# Power.net
KiCad netlist of a schematic drawn in Altium Designer
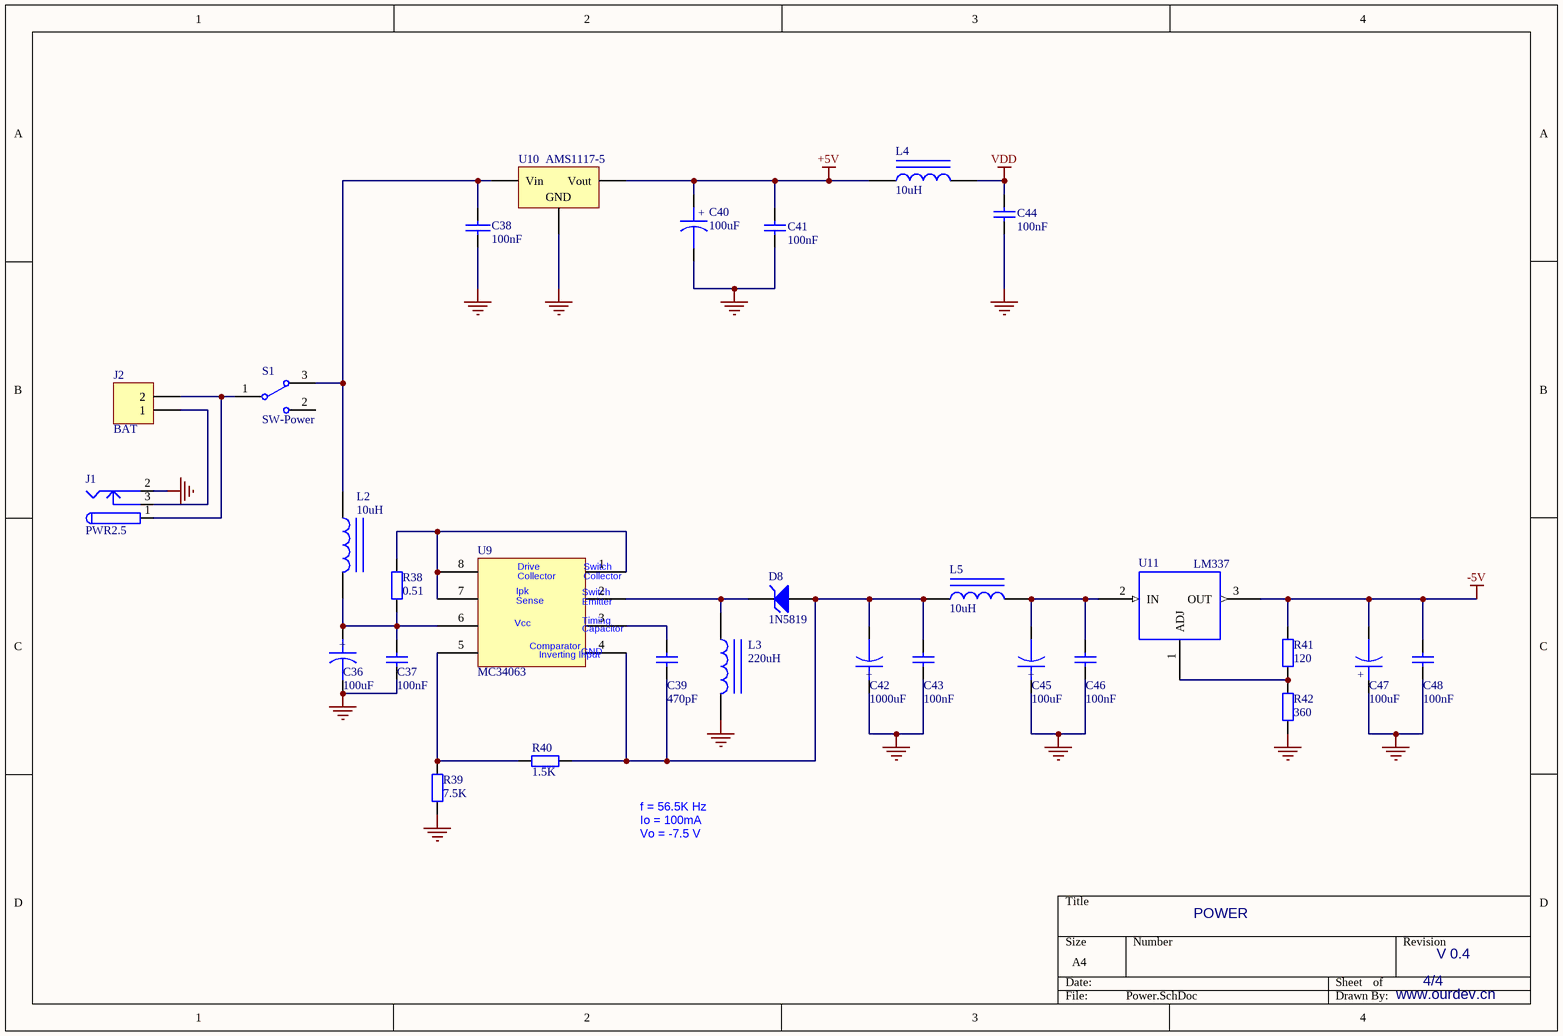
[diagram p0: Power.SchDoc]

(export (version "E")
  (design (tool "Eeschema 10.0.6"))
  (components
    (comp (ref "C36")
      (value "100uF")
      (footprint "Cap 3X6")
      (description "Capacitor")
      (libsource (lib "*") (part "CAPACITOR POL"))
    )
    (comp (ref "C37")
      (value "100nF")
      (footprint "CC2012-0805")
      (description "Capacitor")
      (fields (field (name "PUBLISHER") "Altium Limited"))
      (libsource (lib "*") (part "Cap"))
    )
    (comp (ref "C38")
      (value "100nF")
      (footprint "CC2012-0805")
      (description "Capacitor")
      (libsource (lib "*") (part "CAP"))
    )
    (comp (ref "C39")
      (value "470pF")
      (footprint "CC2012-0805")
      (description "Capacitor")
      (fields (field (name "PUBLISHER") "Altium Limited"))
      (libsource (lib "*") (part "Cap"))
    )
    (comp (ref "C40")
      (value "100uF")
      (footprint "Cap 3X6")
      (description "Capacitor")
      (libsource (lib "") (part "CAPACITOR POL_1"))
    )
    (comp (ref "C41")
      (value "100nF")
      (footprint "CC2012-0805")
      (description "Capacitor")
      (fields (field (name "PUBLISHER") "Altium Limited"))
      (libsource (lib "*") (part "Cap"))
    )
    (comp (ref "C42")
      (value "1000uF")
      (footprint "Cap 3X6")
      (description "Capacitor")
      (libsource (lib "*") (part "CAPACITOR POL"))
    )
    (comp (ref "C43")
      (value "100nF")
      (footprint "CC2012-0805")
      (description "Capacitor")
      (fields (field (name "PUBLISHER") "Altium Limited"))
      (libsource (lib "*") (part "Cap"))
    )
    (comp (ref "C44")
      (value "100nF")
      (footprint "CC2012-0805")
      (description "Capacitor")
      (fields (field (name "PUBLISHER") "Altium Limited"))
      (libsource (lib "*") (part "Cap"))
    )
    (comp (ref "C45")
      (value "100uF")
      (footprint "Cap 3X6")
      (description "Capacitor")
      (libsource (lib "*") (part "CAPACITOR POL"))
    )
    (comp (ref "C46")
      (value "100nF")
      (footprint "CC2012-0805")
      (description "Capacitor")
      (fields (field (name "PUBLISHER") "Altium Limited"))
      (libsource (lib "*") (part "Cap"))
    )
    (comp (ref "C47")
      (value "100uF")
      (footprint "Cap 3X6")
      (description "Capacitor")
      (libsource (lib "") (part "CAPACITOR POL_1"))
    )
    (comp (ref "C48")
      (value "100nF")
      (footprint "CC2012-0805")
      (description "Capacitor")
      (fields (field (name "PUBLISHER") "Altium Limited"))
      (libsource (lib "*") (part "Cap"))
    )
    (comp (ref "D8")
      (value "1N5819")
      (footprint "SMC")
      (description "Zener Diode")
      (fields (field (name "PUBLISHER") "Altium Limited"))
      (libsource (lib "Miscellaneous Devices") (part "D Zener"))
    )
    (comp (ref "J1")
      (value "PWR2.5")
      (footprint "DC JACK")
      (description "Low Voltage Power Supply Connector")
      (fields (field (name "PUBLISHER") "Altium Limited"))
      (libsource (lib "Miscellaneous Connectors") (part "PWR2.5"))
    )
    (comp (ref "J2")
      (value "BAT")
      (footprint "HDR1X2")
      (description "Header, 2-Pin")
      (fields (field (name "PUBLISHER") "Altium Limited"))
      (libsource (lib "Miscellaneous Connectors") (part "Header 2"))
    )
    (comp (ref "L2")
      (value "10uH")
      (footprint "L1.4/3")
      (description "Magnetic-Core Inductor")
      (fields (field (name "PUBLISHER") "Altium Limited"))
      (libsource (lib "Miscellaneous Devices") (part "Inductor Iron"))
    )
    (comp (ref "L3")
      (value "220uH")
      (footprint "L1.4/3")
      (description "Magnetic-Core Inductor")
      (fields (field (name "PUBLISHER") "Altium Limited"))
      (libsource (lib "Miscellaneous Devices") (part "Inductor Iron"))
    )
    (comp (ref "L4")
      (value "10uH")
      (footprint "L1.4/3")
      (description "Magnetic-Core Inductor")
      (fields (field (name "PUBLISHER") "Altium Limited"))
      (libsource (lib "Miscellaneous Devices") (part "Inductor Iron"))
    )
    (comp (ref "L5")
      (value "10uH")
      (footprint "L1.4/3")
      (description "Magnetic-Core Inductor")
      (fields (field (name "PUBLISHER") "Altium Limited"))
      (libsource (lib "Miscellaneous Devices") (part "Inductor Iron"))
    )
    (comp (ref "R38")
      (value "0.51")
      (footprint "R-1206")
      (description "Resistor")
      (fields (field (name "PUBLISHER") "Altium Limited"))
      (libsource (lib "Miscellaneous Devices") (part "Res2"))
    )
    (comp (ref "R39")
      (value "7.5K")
      (footprint "CR2012-0805")
      (description "Resistor")
      (fields (field (name "PUBLISHER") "Altium Limited"))
      (libsource (lib "Miscellaneous Devices") (part "Res2"))
    )
    (comp (ref "R40")
      (value "1.5K")
      (footprint "CR2012-0805")
      (description "Resistor")
      (fields (field (name "PUBLISHER") "Altium Limited"))
      (libsource (lib "") (part "Res2_1"))
    )
    (comp (ref "R41")
      (value "120")
      (footprint "CR2012-0805")
      (description "Resistor")
      (fields (field (name "PUBLISHER") "Altium Limited"))
      (libsource (lib "Miscellaneous Devices") (part "Res2"))
    )
    (comp (ref "R42")
      (value "360")
      (footprint "CR2012-0805")
      (description "Resistor")
      (fields (field (name "PUBLISHER") "Altium Limited"))
      (libsource (lib "Miscellaneous Devices") (part "Res2"))
    )
    (comp (ref "S1")
      (value "SW-Power")
      (footprint "SW-6B")
      (description "SPDT Subminiature Toggle Switch, Right Angle Mounting, Vertical Actuation")
      (fields (field (name "PUBLISHER") "Altium Limited"))
      (libsource (lib "Miscellaneous Devices") (part "SW-SPDT"))
    )
    (comp (ref "U9") (value "MC34063") (footprint "SO-8") (libsource (lib "MC34063") (part "MC34063")))
    (comp (ref "U10")
      (value "AMS1117-5")
      (footprint "SOT-223")
      (description "Voltage Regulator")
      (fields (field (name "PUBLISHER") "Altium Limited"))
      (libsource (lib "Miscellaneous Devices") (part "Volt Reg"))
    )
    (comp (ref "U11") (value "LM337") (footprint "D2PAK") (libsource (lib "LM337") (part "LM337")))
  )
  (nets
    (net (code "1") (name "+5V") (class "Default")
      (node (ref "C40") (pin "1") (pinfunction "1_1") (pintype "passive"))
      (node (ref "C41") (pin "1") (pinfunction "1_1") (pintype "passive"))
      (node (ref "L4") (pin "1") (pinfunction "1_1") (pintype "passive"))
      (node (ref "U10") (pin "2") (pinfunction "Vout_2") (pintype "passive"))
    )
    (net (code "2") (name "-5V") (class "Default")
      (node (ref "C47") (pin "2") (pinfunction "2_2") (pintype "passive"))
      (node (ref "C48") (pin "1") (pinfunction "1_1") (pintype "passive"))
      (node (ref "R41") (pin "2") (pinfunction "2_2") (pintype "passive"))
      (node (ref "U11") (pin "3") (pinfunction "OUT_3") (pintype "output"))
    )
    (net (code "3") (name "GND") (class "Default")
      (node (ref "C36") (pin "2") (pinfunction "2_2") (pintype "passive"))
      (node (ref "C37") (pin "2") (pinfunction "2_2") (pintype "passive"))
      (node (ref "C38") (pin "2") (pinfunction "2_2") (pintype "passive"))
      (node (ref "C40") (pin "2") (pinfunction "2_2") (pintype "passive"))
      (node (ref "C41") (pin "2") (pinfunction "2_2") (pintype "passive"))
      (node (ref "C42") (pin "1") (pinfunction "1_1") (pintype "passive"))
      (node (ref "C43") (pin "2") (pinfunction "2_2") (pintype "passive"))
      (node (ref "C44") (pin "2") (pinfunction "2_2") (pintype "passive"))
      (node (ref "C45") (pin "1") (pinfunction "1_1") (pintype "passive"))
      (node (ref "C46") (pin "2") (pinfunction "2_2") (pintype "passive"))
      (node (ref "C47") (pin "1") (pinfunction "1_1") (pintype "passive"))
      (node (ref "C48") (pin "2") (pinfunction "2_2") (pintype "passive"))
      (node (ref "J1") (pin "2") (pinfunction "2_2") (pintype "power_in"))
      (node (ref "L3") (pin "2") (pinfunction "2_2") (pintype "passive"))
      (node (ref "R39") (pin "1") (pinfunction "1_1") (pintype "passive"))
      (node (ref "R42") (pin "1") (pinfunction "1_1") (pintype "passive"))
      (node (ref "U10") (pin "1") (pinfunction "GND_1") (pintype "passive"))
    )
    (net (code "4") (name "Net-(C36-Pad1)") (class "Default")
      (node (ref "C36") (pin "1") (pinfunction "1_1") (pintype "passive"))
      (node (ref "C37") (pin "1") (pinfunction "1_1") (pintype "passive"))
      (node (ref "L2") (pin "2") (pinfunction "2_2") (pintype "passive"))
      (node (ref "R38") (pin "1") (pinfunction "1_1") (pintype "passive"))
      (node (ref "U9") (pin "6") (pinfunction "6_6") (pintype "power_in"))
    )
    (net (code "5") (name "Net-(C39-Pad1)") (class "Default")
      (node (ref "C39") (pin "1") (pinfunction "1_1") (pintype "passive"))
      (node (ref "U9") (pin "3") (pinfunction "3_3") (pintype "power_in"))
    )
    (net (code "6") (name "Net-(D8-A)") (class "Default")
      (node (ref "C39") (pin "2") (pinfunction "2_2") (pintype "passive"))
      (node (ref "C42") (pin "2") (pinfunction "2_2") (pintype "passive"))
      (node (ref "C43") (pin "1") (pinfunction "1_1") (pintype "passive"))
      (node (ref "D8") (pin "1") (pinfunction "A_1") (pintype "passive"))
      (node (ref "L5") (pin "1") (pinfunction "1_1") (pintype "passive"))
      (node (ref "R40") (pin "2") (pinfunction "2_2") (pintype "passive"))
      (node (ref "U9") (pin "4") (pinfunction "4_4") (pintype "power_in"))
    )
    (net (code "7") (name "Net-(D8-K)") (class "Default")
      (node (ref "D8") (pin "2") (pinfunction "K_2") (pintype "passive"))
      (node (ref "L3") (pin "1") (pinfunction "1_1") (pintype "passive"))
      (node (ref "U9") (pin "2") (pinfunction "2_2") (pintype "power_in"))
    )
    (net (code "8") (name "Net-(J1-Pad1)") (class "Default")
      (node (ref "J1") (pin "1") (pinfunction "1_1") (pintype "power_in"))
      (node (ref "J2") (pin "2") (pinfunction "2_2") (pintype "passive"))
      (node (ref "S1") (pin "1") (pinfunction "1_1") (pintype "passive"))
    )
    (net (code "9") (name "Net-(J1-Pad3)") (class "Default")
      (node (ref "J1") (pin "3") (pinfunction "3_3") (pintype "power_in"))
      (node (ref "J2") (pin "1") (pinfunction "1_1") (pintype "passive"))
    )
    (net (code "10") (name "Net-(R38-Pad2)") (class "Default")
      (node (ref "R38") (pin "2") (pinfunction "2_2") (pintype "passive"))
      (node (ref "U9") (pin "1") (pinfunction "1_1") (pintype "power_in"))
      (node (ref "U9") (pin "7") (pinfunction "7_7") (pintype "power_in"))
      (node (ref "U9") (pin "8") (pinfunction "8_8") (pintype "power_in"))
    )
    (net (code "11") (name "Net-(R39-Pad2)") (class "Default")
      (node (ref "R39") (pin "2") (pinfunction "2_2") (pintype "passive"))
      (node (ref "R40") (pin "1") (pinfunction "1_1") (pintype "passive"))
      (node (ref "U9") (pin "5") (pinfunction "5_5") (pintype "power_in"))
    )
    (net (code "12") (name "Net-(U10-Vin)") (class "Default")
      (node (ref "C38") (pin "1") (pinfunction "1_1") (pintype "passive"))
      (node (ref "L2") (pin "1") (pinfunction "1_1") (pintype "passive"))
      (node (ref "S1") (pin "3") (pinfunction "3_3") (pintype "passive"))
      (node (ref "U10") (pin "3") (pinfunction "Vin_3") (pintype "passive"))
    )
    (net (code "13") (name "Net-(U11-ADJ)") (class "Default")
      (node (ref "R41") (pin "1") (pinfunction "1_1") (pintype "passive"))
      (node (ref "R42") (pin "2") (pinfunction "2_2") (pintype "passive"))
      (node (ref "U11") (pin "1") (pinfunction "ADJ_1") (pintype "power_in"))
    )
    (net (code "14") (name "Net-(U11-IN)") (class "Default")
      (node (ref "C45") (pin "2") (pinfunction "2_2") (pintype "passive"))
      (node (ref "C46") (pin "1") (pinfunction "1_1") (pintype "passive"))
      (node (ref "L5") (pin "2") (pinfunction "2_2") (pintype "passive"))
      (node (ref "U11") (pin "2") (pinfunction "IN_2") (pintype "input"))
    )
    (net (code "15") (name "VDD") (class "Default")
      (node (ref "C44") (pin "1") (pinfunction "1_1") (pintype "passive"))
      (node (ref "L4") (pin "2") (pinfunction "2_2") (pintype "passive"))
    )
    (net (code "16") (name "unconnected-(S1-Pad2)") (class "Default")
      (node (ref "S1") (pin "2") (pinfunction "2_2") (pintype "passive"))
    )
  )
)
